# DAU_Kupplung_1_phasig_V1_9.net
KiCad netlist of a schematic drawn in EAGLE
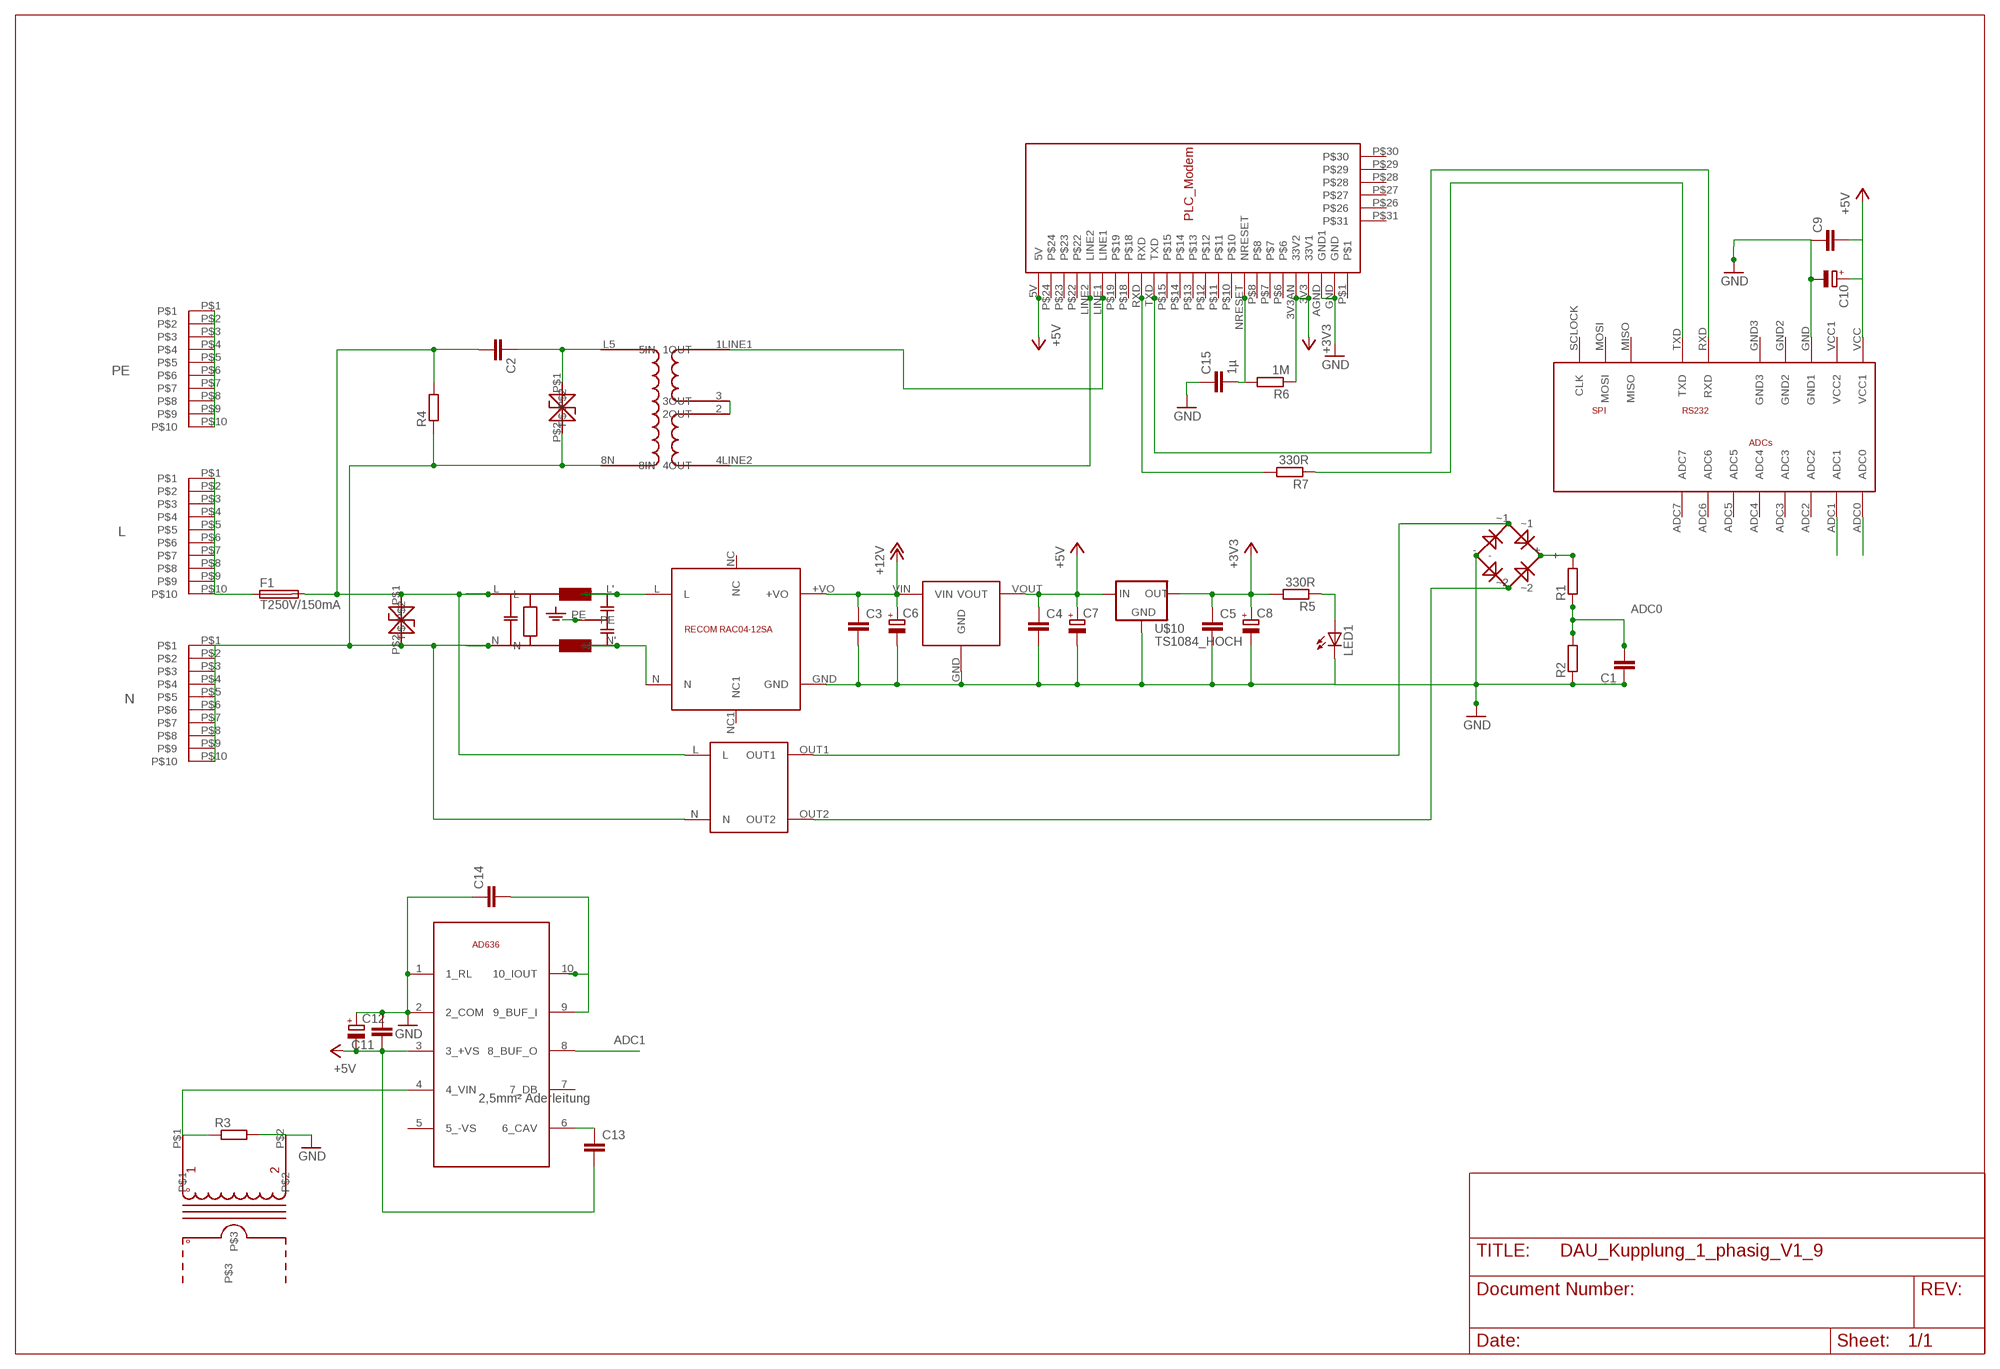
[diagram p0: schematic, sheet 1]

(export (version "E")
  (design (tool "Eeschema 10.0.6"))
  (components
    (comp (ref "C1")
      (value "C2,5-3")
      (footprint "eagle-import:C2.5-3")
      (libsource (lib "eagle-import") (part "C2,5-3"))
    )
    (comp (ref "C2")
      (value "C-EU225-087X268")
      (footprint "eagle-import:C225-087X268")
      (libsource (lib "eagle-import") (part "resistor_C-EU225-087X268"))
    )
    (comp (ref "C3")
      (value "C-EU025-040X050")
      (footprint "eagle-import:C025-040X050")
      (libsource (lib "eagle-import") (part "resistor_C-EU025-040X050"))
    )
    (comp (ref "C4")
      (value "C-EU025-040X050")
      (footprint "eagle-import:C025-040X050")
      (libsource (lib "eagle-import") (part "resistor_C-EU025-040X050"))
    )
    (comp (ref "C5")
      (value "C-EU025-040X050")
      (footprint "eagle-import:C025-040X050")
      (libsource (lib "eagle-import") (part "resistor_C-EU025-040X050"))
    )
    (comp (ref "C6")
      (value "CPOL-EUE2.5-6")
      (footprint "eagle-import:E2,5-6")
      (libsource (lib "eagle-import") (part "resistor_CPOL-EUE2.5-6"))
    )
    (comp (ref "C7")
      (value "CPOL-EUE2.5-6")
      (footprint "eagle-import:E2,5-6")
      (libsource (lib "eagle-import") (part "resistor_CPOL-EUE2.5-6"))
    )
    (comp (ref "C8")
      (value "CPOL-EUE2.5-6")
      (footprint "eagle-import:E2,5-6")
      (libsource (lib "eagle-import") (part "resistor_CPOL-EUE2.5-6"))
    )
    (comp (ref "C9")
      (value "C-EU025-040X050")
      (footprint "eagle-import:C025-040X050")
      (libsource (lib "eagle-import") (part "C-EU025-040X050"))
    )
    (comp (ref "C10")
      (value "CPOL-EUE2,5-6E")
      (footprint "eagle-import:E2,5-6E")
      (libsource (lib "eagle-import") (part "CPOL-EUE2,5-6E"))
    )
    (comp (ref "C11")
      (value "C-EU025-040X050")
      (footprint "eagle-import:C025-040X050")
      (libsource (lib "eagle-import") (part "C-EU025-040X050"))
    )
    (comp (ref "C12")
      (value "CPOL-EUE2,5-6E")
      (footprint "eagle-import:E2,5-6E")
      (libsource (lib "eagle-import") (part "CPOL-EUE2,5-6E"))
    )
    (comp (ref "C13")
      (value "C-EU025-040X050")
      (footprint "eagle-import:C025-040X050")
      (libsource (lib "eagle-import") (part "C-EU025-040X050"))
    )
    (comp (ref "C14")
      (value "C-EU025-040X050")
      (footprint "eagle-import:C025-040X050")
      (libsource (lib "eagle-import") (part "C-EU025-040X050"))
    )
    (comp (ref "C15")
      (value "1µ")
      (footprint "eagle-import:C025-040X050")
      (libsource (lib "eagle-import") (part "resistor_C-EU025-040X050"))
    )
    (comp (ref "F1")
      (value "T250V/150mA")
      (footprint "eagle-import:TR5")
      (libsource (lib "eagle-import") (part "TR5"))
    )
    (comp (ref "L")
      (value "PRINT_CONNECTOR")
      (footprint "eagle-import:FASTON_DOUBLE")
      (libsource (lib "eagle-import") (part "PRINT_CONNECTOR"))
    )
    (comp (ref "LED1")
      (value "LEDSQR2X5")
      (footprint "eagle-import:LED2X5")
      (libsource (lib "eagle-import") (part "LEDSQR2X5"))
    )
    (comp (ref "N")
      (value "PRINT_CONNECTOR")
      (footprint "eagle-import:FASTON_DOUBLE")
      (libsource (lib "eagle-import") (part "PRINT_CONNECTOR"))
    )
    (comp (ref "PE")
      (value "PRINT_CONNECTOR")
      (footprint "eagle-import:FASTON_DOUBLE")
      (libsource (lib "eagle-import") (part "PRINT_CONNECTOR"))
    )
    (comp (ref "R1")
      (value "R-EU_0204/7")
      (footprint "eagle-import:0204_7")
      (libsource (lib "eagle-import") (part "R-EU_0204/7"))
    )
    (comp (ref "R2")
      (value "R-EU_0204/7")
      (footprint "eagle-import:0204_7")
      (libsource (lib "eagle-import") (part "R-EU_0204/7"))
    )
    (comp (ref "R3")
      (value "R-EU_0204/7")
      (footprint "eagle-import:0204_7")
      (libsource (lib "eagle-import") (part "R-EU_0204/7"))
    )
    (comp (ref "R4")
      (value "R-EU_0204/7")
      (footprint "eagle-import:0204_7")
      (libsource (lib "eagle-import") (part "R-EU_0204/7"))
    )
    (comp (ref "R5")
      (value "330R")
      (footprint "eagle-import:0204_7")
      (libsource (lib "eagle-import") (part "R-EU_0204/7"))
    )
    (comp (ref "R6")
      (value "1M")
      (footprint "eagle-import:0204_7")
      (libsource (lib "eagle-import") (part "R-EU_0204/7"))
    )
    (comp (ref "R7")
      (value "330R")
      (footprint "eagle-import:0204_7")
      (libsource (lib "eagle-import") (part "R-EU_0204/7"))
    )
    (comp (ref "U$1")
      (value "RECOM_RAC04_12SA")
      (footprint "eagle-import:RAC04_12SA")
      (libsource (lib "eagle-import") (part "RECOM_RAC04_12SA"))
    )
    (comp (ref "U$2")
      (value "SICHERHEITSTRAFO")
      (footprint "eagle-import:TRAFO_0,35VA")
      (libsource (lib "eagle-import") (part "SICHERHEITSTRAFO"))
    )
    (comp (ref "U$3")
      (value "ADUC831_MINIMUM")
      (footprint "eagle-import:ADUC_MINIMUM")
      (libsource (lib "eagle-import") (part "ADUC831_MINIMUM"))
    )
    (comp (ref "U$4")
      (value "MODEMSTECKER_KLEINE_PINS")
      (footprint "eagle-import:MODEM_FUSS_KLEINE_PINS")
      (libsource (lib "eagle-import") (part "MODEMSTECKER_KLEINE_PINS"))
    )
    (comp (ref "U$5")
      (value "PLC_UEBERTRAGER_V2")
      (footprint "eagle-import:PLC-UEBERTRAGER_V2")
      (libsource (lib "eagle-import") (part "PLC_UEBERTRAGER_V2"))
    )
    (comp (ref "U$6")
      (value "AC1010")
      (footprint "eagle-import:AC1010")
      (libsource (lib "eagle-import") (part "AC1010"))
    )
    (comp (ref "U$7")
      (value "AD636")
      (footprint "eagle-import:TO100_10PIN")
      (libsource (lib "eagle-import") (part "AD636"))
    )
    (comp (ref "U$8")
      (value "RECTIFIER")
      (footprint "eagle-import:RECTIFIER")
      (libsource (lib "eagle-import") (part "RECTIFIER"))
    )
    (comp (ref "U$9")
      (value "TSV")
      (footprint "eagle-import:TSV")
      (libsource (lib "eagle-import") (part "TSV"))
    )
    (comp (ref "U$10")
      (value "TS1084_HOCH")
      (footprint "eagle-import:TS1084_HOCH")
      (libsource (lib "eagle-import") (part "TS1084_HOCH"))
    )
    (comp (ref "U$11")
      (value "RECOM_785_05")
      (footprint "eagle-import:RECOM785X")
      (libsource (lib "eagle-import") (part "RECOM_785_05"))
    )
    (comp (ref "U$12")
      (value "TSV")
      (footprint "eagle-import:TSV")
      (libsource (lib "eagle-import") (part "TSV"))
    )
    (comp (ref "U$13")
      (value "NETZFILTER_05_A")
      (footprint "eagle-import:NETZFILTER")
      (libsource (lib "eagle-import") (part "NETZFILTER_05_A"))
    )
  )
  (nets
    (net (code "1") (name "+3V3") (class "Default")
      (node (ref "C5") (pin "1") (pinfunction "1_1") (pintype "passive"))
      (node (ref "C8") (pin "+") (pinfunction "+_+") (pintype "passive"))
      (node (ref "R5") (pin "2") (pinfunction "2_2") (pintype "passive"))
      (node (ref "R6") (pin "1") (pinfunction "1_1") (pintype "passive"))
      (node (ref "U$10") (pin "OUT") (pinfunction "OUT_OUT") (pintype "passive"))
      (node (ref "U$4") (pin "3V3") (pinfunction "33V1_3V3") (pintype "bidirectional"))
      (node (ref "U$4") (pin "3V3AN") (pinfunction "33V2_3V3AN") (pintype "bidirectional"))
    )
    (net (code "2") (name "+5V") (class "Default")
      (node (ref "C10") (pin "+") (pinfunction "+_+") (pintype "passive"))
      (node (ref "C11") (pin "1") (pinfunction "1_1") (pintype "passive"))
      (node (ref "C12") (pin "-") (pinfunction "-_-") (pintype "passive"))
      (node (ref "C13") (pin "2") (pinfunction "2_2") (pintype "passive"))
      (node (ref "C4") (pin "1") (pinfunction "1_1") (pintype "passive"))
      (node (ref "C7") (pin "+") (pinfunction "+_+") (pintype "passive"))
      (node (ref "C9") (pin "2") (pinfunction "2_2") (pintype "passive"))
      (node (ref "U$10") (pin "IN") (pinfunction "IN_IN") (pintype "input"))
      (node (ref "U$11") (pin "VOUT") (pinfunction "VOUT_VOUT") (pintype "bidirectional"))
      (node (ref "U$3") (pin "VCC") (pinfunction "VCC1_VCC") (pintype "bidirectional"))
      (node (ref "U$4") (pin "5V") (pinfunction "5V_5V") (pintype "bidirectional"))
      (node (ref "U$7") (pin "3") (pinfunction "3_+VS_3") (pintype "input"))
    )
    (net (code "3") (name "+12V") (class "Default")
      (node (ref "C3") (pin "1") (pinfunction "1_1") (pintype "passive"))
      (node (ref "C6") (pin "+") (pinfunction "+_+") (pintype "passive"))
      (node (ref "U$1") (pin "+VO") (pinfunction "+VO_+VO") (pintype "bidirectional"))
      (node (ref "U$11") (pin "VIN") (pinfunction "VIN_VIN") (pintype "bidirectional"))
    )
    (net (code "4") (name "/ADC0") (class "Default")
      (node (ref "C1") (pin "2") (pinfunction "2_2") (pintype "passive"))
      (node (ref "R1") (pin "1") (pinfunction "1_1") (pintype "passive"))
      (node (ref "R2") (pin "2") (pinfunction "2_2") (pintype "passive"))
      (node (ref "U$3") (pin "ADC0") (pinfunction "ADC0_ADC0") (pintype "bidirectional"))
    )
    (net (code "5") (name "/ADC1") (class "Default")
      (node (ref "U$3") (pin "ADC1") (pinfunction "ADC1_ADC1") (pintype "bidirectional"))
      (node (ref "U$7") (pin "8") (pinfunction "8_BUF_O_8") (pintype "output"))
    )
    (net (code "6") (name "/PE") (class "Default")
      (node (ref "PE") (pin "P$1") (pinfunction "P$1_P$1") (pintype "bidirectional"))
      (node (ref "PE") (pin "P$10") (pinfunction "P$10_P$10") (pintype "bidirectional"))
      (node (ref "PE") (pin "P$2") (pinfunction "P$2_P$2") (pintype "bidirectional"))
      (node (ref "PE") (pin "P$3") (pinfunction "P$3_P$3") (pintype "bidirectional"))
      (node (ref "PE") (pin "P$4") (pinfunction "P$4_P$4") (pintype "bidirectional"))
      (node (ref "PE") (pin "P$5") (pinfunction "P$5_P$5") (pintype "bidirectional"))
      (node (ref "PE") (pin "P$6") (pinfunction "P$6_P$6") (pintype "bidirectional"))
      (node (ref "PE") (pin "P$7") (pinfunction "P$7_P$7") (pintype "bidirectional"))
      (node (ref "PE") (pin "P$8") (pinfunction "P$8_P$8") (pintype "bidirectional"))
      (node (ref "PE") (pin "P$9") (pinfunction "P$9_P$9") (pintype "bidirectional"))
      (node (ref "U$13") (pin "PE") (pinfunction "PE_PE") (pintype "input"))
    )
    (net (code "7") (name "GND") (class "Default")
      (node (ref "C1") (pin "1") (pinfunction "1_1") (pintype "passive"))
      (node (ref "C10") (pin "-") (pinfunction "-_-") (pintype "passive"))
      (node (ref "C11") (pin "2") (pinfunction "2_2") (pintype "passive"))
      (node (ref "C12") (pin "+") (pinfunction "+_+") (pintype "passive"))
      (node (ref "C14") (pin "1") (pinfunction "1_1") (pintype "passive"))
      (node (ref "C15") (pin "1") (pinfunction "1_1") (pintype "passive"))
      (node (ref "C3") (pin "2") (pinfunction "2_2") (pintype "passive"))
      (node (ref "C4") (pin "2") (pinfunction "2_2") (pintype "passive"))
      (node (ref "C5") (pin "2") (pinfunction "2_2") (pintype "passive"))
      (node (ref "C6") (pin "-") (pinfunction "-_-") (pintype "passive"))
      (node (ref "C7") (pin "-") (pinfunction "-_-") (pintype "passive"))
      (node (ref "C8") (pin "-") (pinfunction "-_-") (pintype "passive"))
      (node (ref "C9") (pin "1") (pinfunction "1_1") (pintype "passive"))
      (node (ref "LED1") (pin "K") (pinfunction "C_K") (pintype "passive"))
      (node (ref "R2") (pin "1") (pinfunction "1_1") (pintype "passive"))
      (node (ref "R3") (pin "2") (pinfunction "2_2") (pintype "passive"))
      (node (ref "U$1") (pin "GND") (pinfunction "GND_GND") (pintype "bidirectional"))
      (node (ref "U$10") (pin "GND") (pinfunction "GND_GND") (pintype "input"))
      (node (ref "U$11") (pin "GND") (pinfunction "GND_GND") (pintype "bidirectional"))
      (node (ref "U$3") (pin "GND") (pinfunction "GND1_GND") (pintype "bidirectional"))
      (node (ref "U$4") (pin "AGND") (pinfunction "GND1_AGND") (pintype "bidirectional"))
      (node (ref "U$4") (pin "GND") (pinfunction "GND_GND") (pintype "bidirectional"))
      (node (ref "U$6") (pin "P$2") (pinfunction "P$2_P$2") (pintype "bidirectional"))
      (node (ref "U$7") (pin "1") (pinfunction "1_RL_1") (pintype "bidirectional"))
      (node (ref "U$7") (pin "2") (pinfunction "2_COM_2") (pintype "bidirectional"))
      (node (ref "U$8") (pin "-") (pinfunction "-_-") (pintype "bidirectional"))
    )
    (net (code "8") (name "Net-(C2-Pad2)") (class "Default")
      (node (ref "C2") (pin "2") (pinfunction "2_2") (pintype "passive"))
      (node (ref "F1") (pin "2") (pinfunction "2_2") (pintype "passive"))
      (node (ref "R4") (pin "2") (pinfunction "2_2") (pintype "passive"))
      (node (ref "U$13") (pin "L") (pinfunction "L_L") (pintype "bidirectional"))
      (node (ref "U$2") (pin "L") (pinfunction "L_L") (pintype "bidirectional"))
      (node (ref "U$9") (pin "P$1") (pinfunction "P$1_P$1") (pintype "bidirectional"))
    )
    (net (code "9") (name "Net-(C15-Pad2)") (class "Default")
      (node (ref "C15") (pin "2") (pinfunction "2_2") (pintype "passive"))
      (node (ref "R6") (pin "2") (pinfunction "2_2") (pintype "passive"))
      (node (ref "U$4") (pin "NRESET") (pinfunction "NRESET_NRESET") (pintype "bidirectional"))
    )
    (net (code "10") (name "Net-(F1-Pad1)") (class "Default")
      (node (ref "F1") (pin "1") (pinfunction "1_1") (pintype "passive"))
      (node (ref "L") (pin "P$1") (pinfunction "P$1_P$1") (pintype "bidirectional"))
      (node (ref "L") (pin "P$10") (pinfunction "P$10_P$10") (pintype "bidirectional"))
      (node (ref "L") (pin "P$2") (pinfunction "P$2_P$2") (pintype "bidirectional"))
      (node (ref "L") (pin "P$3") (pinfunction "P$3_P$3") (pintype "bidirectional"))
      (node (ref "L") (pin "P$4") (pinfunction "P$4_P$4") (pintype "bidirectional"))
      (node (ref "L") (pin "P$5") (pinfunction "P$5_P$5") (pintype "bidirectional"))
      (node (ref "L") (pin "P$6") (pinfunction "P$6_P$6") (pintype "bidirectional"))
      (node (ref "L") (pin "P$7") (pinfunction "P$7_P$7") (pintype "bidirectional"))
      (node (ref "L") (pin "P$8") (pinfunction "P$8_P$8") (pintype "bidirectional"))
      (node (ref "L") (pin "P$9") (pinfunction "P$9_P$9") (pintype "bidirectional"))
    )
    (net (code "11") (name "Net-(LED1-PadA)") (class "Default")
      (node (ref "LED1") (pin "A") (pinfunction "A_A") (pintype "passive"))
      (node (ref "R5") (pin "1") (pinfunction "1_1") (pintype "passive"))
    )
    (net (code "12") (name "Net-(R1-Pad2)") (class "Default")
      (node (ref "R1") (pin "2") (pinfunction "2_2") (pintype "passive"))
      (node (ref "U$8") (pin "+") (pinfunction "+_+") (pintype "bidirectional"))
    )
    (net (code "13") (name "Net-(R7-Pad1)") (class "Default")
      (node (ref "R7") (pin "1") (pinfunction "1_1") (pintype "passive"))
      (node (ref "U$3") (pin "TXD") (pinfunction "TXD_TXD") (pintype "bidirectional"))
    )
    (net (code "14") (name "Net-(R7-Pad2)") (class "Default")
      (node (ref "R7") (pin "2") (pinfunction "2_2") (pintype "passive"))
      (node (ref "U$4") (pin "RXD") (pinfunction "RXD_RXD") (pintype "bidirectional"))
    )
    (net (code "15") (name "Net-(U$1-PadL)") (class "Default")
      (node (ref "U$1") (pin "L") (pinfunction "L_L") (pintype "bidirectional"))
      (node (ref "U$13") (pin "L'") (pinfunction "L'_L'") (pintype "bidirectional"))
    )
    (net (code "16") (name "Net-(U$1-PadN)") (class "Default")
      (node (ref "U$1") (pin "N") (pinfunction "N_N") (pintype "bidirectional"))
      (node (ref "U$13") (pin "N'") (pinfunction "N'_N'") (pintype "bidirectional"))
    )
    (net (code "17") (name "Net-(U$3-PadRXD)") (class "Default")
      (node (ref "U$3") (pin "RXD") (pinfunction "RXD_RXD") (pintype "bidirectional"))
      (node (ref "U$4") (pin "TXD") (pinfunction "TXD_TXD") (pintype "bidirectional"))
    )
    (net (code "18") (name "Net-(U$5-1OUT)") (class "Default")
      (node (ref "U$4") (pin "LINE1") (pinfunction "LINE1_LINE1") (pintype "bidirectional"))
      (node (ref "U$5") (pin "1LINE1") (pinfunction "1OUT_1LINE1") (pintype "output"))
    )
    (net (code "19") (name "Net-(U$5-2OUT)") (class "Default")
      (node (ref "U$5") (pin "2") (pinfunction "2OUT_2") (pintype "output"))
      (node (ref "U$5") (pin "3") (pinfunction "3OUT_3") (pintype "output"))
    )
    (net (code "20") (name "Net-(U$5-4OUT)") (class "Default")
      (node (ref "U$4") (pin "LINE2") (pinfunction "LINE2_LINE2") (pintype "bidirectional"))
      (node (ref "U$5") (pin "4LINE2") (pinfunction "4OUT_4LINE2") (pintype "output"))
    )
    (net (code "21") (name "Net-(U$5-5IN)") (class "Default")
      (node (ref "C2") (pin "1") (pinfunction "1_1") (pintype "passive"))
      (node (ref "U$12") (pin "P$1") (pinfunction "P$1_P$1") (pintype "bidirectional"))
      (node (ref "U$5") (pin "L5") (pinfunction "5IN_L5") (pintype "input"))
    )
    (net (code "22") (name "Net-(U$5-8IN)") (class "Default")
      (node (ref "N") (pin "P$1") (pinfunction "P$1_P$1") (pintype "bidirectional"))
      (node (ref "N") (pin "P$10") (pinfunction "P$10_P$10") (pintype "bidirectional"))
      (node (ref "N") (pin "P$2") (pinfunction "P$2_P$2") (pintype "bidirectional"))
      (node (ref "N") (pin "P$3") (pinfunction "P$3_P$3") (pintype "bidirectional"))
      (node (ref "N") (pin "P$4") (pinfunction "P$4_P$4") (pintype "bidirectional"))
      (node (ref "N") (pin "P$5") (pinfunction "P$5_P$5") (pintype "bidirectional"))
      (node (ref "N") (pin "P$6") (pinfunction "P$6_P$6") (pintype "bidirectional"))
      (node (ref "N") (pin "P$7") (pinfunction "P$7_P$7") (pintype "bidirectional"))
      (node (ref "N") (pin "P$8") (pinfunction "P$8_P$8") (pintype "bidirectional"))
      (node (ref "N") (pin "P$9") (pinfunction "P$9_P$9") (pintype "bidirectional"))
      (node (ref "R4") (pin "1") (pinfunction "1_1") (pintype "passive"))
      (node (ref "U$12") (pin "P$2") (pinfunction "P$2_P$2") (pintype "bidirectional"))
      (node (ref "U$13") (pin "N") (pinfunction "N_N") (pintype "bidirectional"))
      (node (ref "U$2") (pin "N") (pinfunction "N_N") (pintype "bidirectional"))
      (node (ref "U$5") (pin "8N") (pinfunction "8IN_8N") (pintype "input"))
      (node (ref "U$9") (pin "P$2") (pinfunction "P$2_P$2") (pintype "bidirectional"))
    )
    (net (code "23") (name "Net-(U$7-4_VIN)") (class "Default")
      (node (ref "R3") (pin "1") (pinfunction "1_1") (pintype "passive"))
      (node (ref "U$6") (pin "P$1") (pinfunction "P$1_P$1") (pintype "bidirectional"))
      (node (ref "U$7") (pin "4") (pinfunction "4_VIN_4") (pintype "input"))
    )
    (net (code "24") (name "Net-(U$7-6_CAV)") (class "Default")
      (node (ref "C13") (pin "1") (pinfunction "1_1") (pintype "passive"))
      (node (ref "U$7") (pin "6") (pinfunction "6_CAV_6") (pintype "input"))
    )
    (net (code "25") (name "Net-(U$7-10_IOUT)") (class "Default")
      (node (ref "C14") (pin "2") (pinfunction "2_2") (pintype "passive"))
      (node (ref "U$7") (pin "10") (pinfunction "10_IOUT_10") (pintype "output"))
      (node (ref "U$7") (pin "9") (pinfunction "9_BUF_I_9") (pintype "input"))
    )
    (net (code "26") (name "Net-(U$8-~{1})") (class "Default")
      (node (ref "U$2") (pin "OUT1") (pinfunction "OUT1_OUT1") (pintype "bidirectional"))
      (node (ref "U$8") (pin "~1") (pinfunction "~{1}_~1") (pintype "bidirectional"))
    )
    (net (code "27") (name "Net-(U$8-~{2})") (class "Default")
      (node (ref "U$2") (pin "OUT2") (pinfunction "OUT2_OUT2") (pintype "bidirectional"))
      (node (ref "U$8") (pin "~2") (pinfunction "~{2}_~2") (pintype "bidirectional"))
    )
    (net (code "28") (name "unconnected-(U$1-PadNC)") (class "Default")
      (node (ref "U$1") (pin "NC") (pinfunction "NC_NC") (pintype "bidirectional"))
    )
    (net (code "29") (name "unconnected-(U$1-PadNC1)") (class "Default")
      (node (ref "U$1") (pin "NC1") (pinfunction "NC1_NC1") (pintype "bidirectional"))
    )
    (net (code "30") (name "unconnected-(U$3-CLK-PadSCLOCK)") (class "Default")
      (node (ref "U$3") (pin "SCLOCK") (pinfunction "CLK_SCLOCK") (pintype "bidirectional"))
    )
    (net (code "31") (name "unconnected-(U$3-PadADC2)") (class "Default")
      (node (ref "U$3") (pin "ADC2") (pinfunction "ADC2_ADC2") (pintype "bidirectional"))
    )
    (net (code "32") (name "unconnected-(U$3-PadADC3)") (class "Default")
      (node (ref "U$3") (pin "ADC3") (pinfunction "ADC3_ADC3") (pintype "bidirectional"))
    )
    (net (code "33") (name "unconnected-(U$3-PadADC4)") (class "Default")
      (node (ref "U$3") (pin "ADC4") (pinfunction "ADC4_ADC4") (pintype "bidirectional"))
    )
    (net (code "34") (name "unconnected-(U$3-PadADC5)") (class "Default")
      (node (ref "U$3") (pin "ADC5") (pinfunction "ADC5_ADC5") (pintype "bidirectional"))
    )
    (net (code "35") (name "unconnected-(U$3-PadADC6)") (class "Default")
      (node (ref "U$3") (pin "ADC6") (pinfunction "ADC6_ADC6") (pintype "bidirectional"))
    )
    (net (code "36") (name "unconnected-(U$3-PadADC7)") (class "Default")
      (node (ref "U$3") (pin "ADC7") (pinfunction "ADC7_ADC7") (pintype "bidirectional"))
    )
    (net (code "37") (name "unconnected-(U$3-PadGND2)") (class "Default")
      (node (ref "U$3") (pin "GND2") (pinfunction "GND2_GND2") (pintype "bidirectional"))
    )
    (net (code "38") (name "unconnected-(U$3-PadGND3)") (class "Default")
      (node (ref "U$3") (pin "GND3") (pinfunction "GND3_GND3") (pintype "bidirectional"))
    )
    (net (code "39") (name "unconnected-(U$3-PadMISO)") (class "Default")
      (node (ref "U$3") (pin "MISO") (pinfunction "MISO_MISO") (pintype "bidirectional"))
    )
    (net (code "40") (name "unconnected-(U$3-PadMOSI)") (class "Default")
      (node (ref "U$3") (pin "MOSI") (pinfunction "MOSI_MOSI") (pintype "bidirectional"))
    )
    (net (code "41") (name "unconnected-(U$3-VCC2-PadVCC1)") (class "Default")
      (node (ref "U$3") (pin "VCC1") (pinfunction "VCC2_VCC1") (pintype "bidirectional"))
    )
    (net (code "42") (name "unconnected-(U$4-PadP$1)") (class "Default")
      (node (ref "U$4") (pin "P$1") (pinfunction "P$1_P$1") (pintype "bidirectional"))
    )
    (net (code "43") (name "unconnected-(U$4-PadP$6)") (class "Default")
      (node (ref "U$4") (pin "P$6") (pinfunction "P$6_P$6") (pintype "bidirectional"))
    )
    (net (code "44") (name "unconnected-(U$4-PadP$7)") (class "Default")
      (node (ref "U$4") (pin "P$7") (pinfunction "P$7_P$7") (pintype "bidirectional"))
    )
    (net (code "45") (name "unconnected-(U$4-PadP$8)") (class "Default")
      (node (ref "U$4") (pin "P$8") (pinfunction "P$8_P$8") (pintype "bidirectional"))
    )
    (net (code "46") (name "unconnected-(U$4-PadP$10)") (class "Default")
      (node (ref "U$4") (pin "P$10") (pinfunction "P$10_P$10") (pintype "bidirectional"))
    )
    (net (code "47") (name "unconnected-(U$4-PadP$11)") (class "Default")
      (node (ref "U$4") (pin "P$11") (pinfunction "P$11_P$11") (pintype "bidirectional"))
    )
    (net (code "48") (name "unconnected-(U$4-PadP$12)") (class "Default")
      (node (ref "U$4") (pin "P$12") (pinfunction "P$12_P$12") (pintype "bidirectional"))
    )
    (net (code "49") (name "unconnected-(U$4-PadP$13)") (class "Default")
      (node (ref "U$4") (pin "P$13") (pinfunction "P$13_P$13") (pintype "bidirectional"))
    )
    (net (code "50") (name "unconnected-(U$4-PadP$14)") (class "Default")
      (node (ref "U$4") (pin "P$14") (pinfunction "P$14_P$14") (pintype "bidirectional"))
    )
    (net (code "51") (name "unconnected-(U$4-PadP$15)") (class "Default")
      (node (ref "U$4") (pin "P$15") (pinfunction "P$15_P$15") (pintype "bidirectional"))
    )
    (net (code "52") (name "unconnected-(U$4-PadP$18)") (class "Default")
      (node (ref "U$4") (pin "P$18") (pinfunction "P$18_P$18") (pintype "bidirectional"))
    )
    (net (code "53") (name "unconnected-(U$4-PadP$19)") (class "Default")
      (node (ref "U$4") (pin "P$19") (pinfunction "P$19_P$19") (pintype "bidirectional"))
    )
    (net (code "54") (name "unconnected-(U$4-PadP$22)") (class "Default")
      (node (ref "U$4") (pin "P$22") (pinfunction "P$22_P$22") (pintype "bidirectional"))
    )
    (net (code "55") (name "unconnected-(U$4-PadP$23)") (class "Default")
      (node (ref "U$4") (pin "P$23") (pinfunction "P$23_P$23") (pintype "bidirectional"))
    )
    (net (code "56") (name "unconnected-(U$4-PadP$24)") (class "Default")
      (node (ref "U$4") (pin "P$24") (pinfunction "P$24_P$24") (pintype "bidirectional"))
    )
    (net (code "57") (name "unconnected-(U$4-PadP$26)") (class "Default")
      (node (ref "U$4") (pin "P$26") (pinfunction "P$26_P$26") (pintype "bidirectional"))
    )
    (net (code "58") (name "unconnected-(U$4-PadP$27)") (class "Default")
      (node (ref "U$4") (pin "P$27") (pinfunction "P$27_P$27") (pintype "bidirectional"))
    )
    (net (code "59") (name "unconnected-(U$4-PadP$28)") (class "Default")
      (node (ref "U$4") (pin "P$28") (pinfunction "P$28_P$28") (pintype "bidirectional"))
    )
    (net (code "60") (name "unconnected-(U$4-PadP$29)") (class "Default")
      (node (ref "U$4") (pin "P$29") (pinfunction "P$29_P$29") (pintype "bidirectional"))
    )
    (net (code "61") (name "unconnected-(U$4-PadP$30)") (class "Default")
      (node (ref "U$4") (pin "P$30") (pinfunction "P$30_P$30") (pintype "bidirectional"))
    )
    (net (code "62") (name "unconnected-(U$4-PadP$31)") (class "Default")
      (node (ref "U$4") (pin "P$31") (pinfunction "P$31_P$31") (pintype "bidirectional"))
    )
    (net (code "63") (name "unconnected-(U$6-PadP$3)") (class "Default")
      (node (ref "U$6") (pin "P$3") (pinfunction "P$3_P$3") (pintype "bidirectional"))
    )
    (net (code "64") (name "unconnected-(U$7-5_-VS-Pad5)") (class "Default")
      (node (ref "U$7") (pin "5") (pinfunction "5_-VS_5") (pintype "input"))
    )
    (net (code "65") (name "unconnected-(U$7-7_DB-Pad7)") (class "Default")
      (node (ref "U$7") (pin "7") (pinfunction "7_DB_7") (pintype "output"))
    )
  )
)
